# twometertx.net
KiCad netlist of a schematic drawn in EAGLE
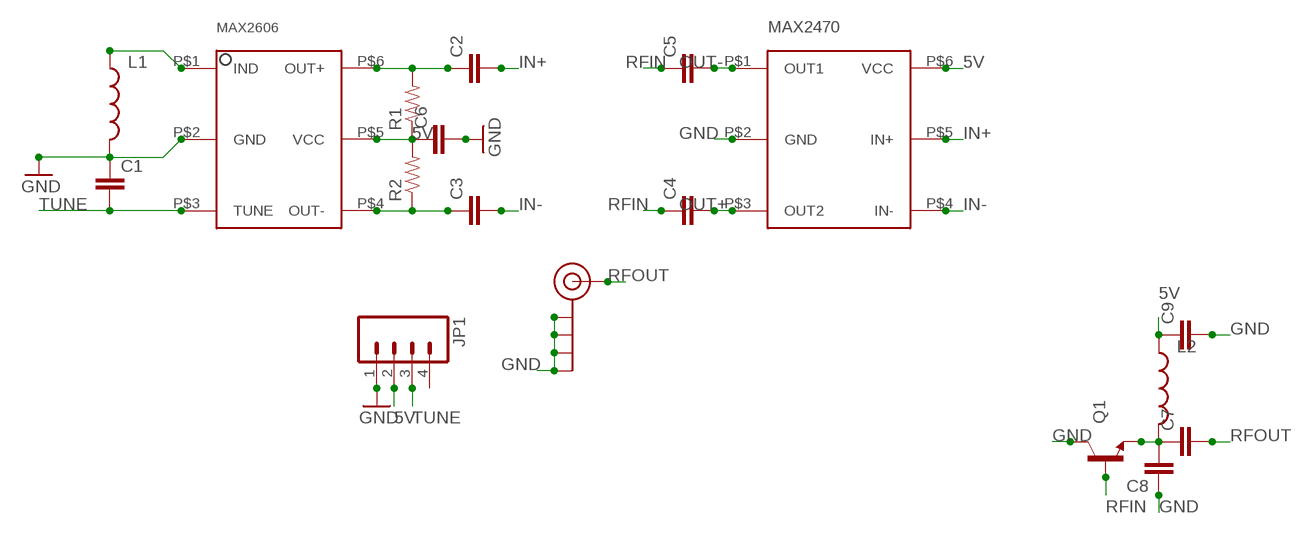
[diagram p0: schematic, sheet 1]

(export (version "E")
  (design (tool "Eeschema 10.0.6"))
  (components
    (comp (ref "C1")
      (value "CAP0805")
      (footprint "eagle-import:0805")
      (libsource (lib "eagle-import") (part "CAP0805"))
    )
    (comp (ref "C2")
      (value "CAP0805")
      (footprint "eagle-import:0805")
      (libsource (lib "eagle-import") (part "CAP0805"))
    )
    (comp (ref "C3")
      (value "CAP0805")
      (footprint "eagle-import:0805")
      (libsource (lib "eagle-import") (part "CAP0805"))
    )
    (comp (ref "C4")
      (value "CAP0805")
      (footprint "eagle-import:0805")
      (libsource (lib "eagle-import") (part "CAP0805"))
    )
    (comp (ref "C5")
      (value "CAP0805")
      (footprint "eagle-import:0805")
      (libsource (lib "eagle-import") (part "CAP0805"))
    )
    (comp (ref "C6")
      (value "CAP0805")
      (footprint "eagle-import:0805")
      (libsource (lib "eagle-import") (part "CAP0805"))
    )
    (comp (ref "C7")
      (value "CAP0805")
      (footprint "eagle-import:0805")
      (libsource (lib "eagle-import") (part "CAP0805"))
    )
    (comp (ref "C8")
      (value "CAP0805")
      (footprint "eagle-import:0805")
      (libsource (lib "eagle-import") (part "CAP0805"))
    )
    (comp (ref "C9")
      (value "CAP0805")
      (footprint "eagle-import:0805")
      (libsource (lib "eagle-import") (part "CAP0805"))
    )
    (comp (ref "J$1")
      (value "SMA_EDGE")
      (footprint "eagle-import:SMA-EDGE")
      (libsource (lib "eagle-import") (part "SMA_EDGE"))
    )
    (comp (ref "JP1")
      (value "M04LONGPADS")
      (footprint "eagle-import:1X04_LONGPADS")
      (libsource (lib "eagle-import") (part "M04LONGPADS"))
    )
    (comp (ref "L1")
      (value "INDUCTOR0805")
      (footprint "eagle-import:0805")
      (libsource (lib "eagle-import") (part "INDUCTOR0805"))
    )
    (comp (ref "L2")
      (value "INDUCTOR0805")
      (footprint "eagle-import:0805")
      (libsource (lib "eagle-import") (part "INDUCTOR0805"))
    )
    (comp (ref "Q1")
      (value "TRANSISTOR_NPNSOT89")
      (footprint "eagle-import:SOT89")
      (libsource (lib "eagle-import") (part "TRANSISTOR_NPNSOT89"))
    )
    (comp (ref "R1")
      (value "RESISTOR0805-RES")
      (footprint "eagle-import:0805")
      (libsource (lib "eagle-import") (part "RESISTOR0805-RES"))
    )
    (comp (ref "R2")
      (value "RESISTOR0805-RES")
      (footprint "eagle-import:0805")
      (libsource (lib "eagle-import") (part "RESISTOR0805-RES"))
    )
    (comp (ref "U$1")
      (value "MAX2606")
      (footprint "eagle-import:MAX2606")
      (libsource (lib "eagle-import") (part "MAX2606"))
    )
    (comp (ref "U$2")
      (value "MAX2470")
      (footprint "eagle-import:MAX2470")
      (libsource (lib "eagle-import") (part "MAX2470"))
    )
  )
  (nets
    (net (code "1") (name "/5V") (class "Default")
      (node (ref "C6") (pin "1") (pinfunction "1_1") (pintype "passive"))
      (node (ref "C9") (pin "1") (pinfunction "1_1") (pintype "passive"))
      (node (ref "JP1") (pin "2") (pinfunction "2_2") (pintype "passive"))
      (node (ref "L2") (pin "1") (pinfunction "1_1") (pintype "passive"))
      (node (ref "R1") (pin "1") (pinfunction "1_1") (pintype "passive"))
      (node (ref "R2") (pin "2") (pinfunction "2_2") (pintype "passive"))
      (node (ref "U$1") (pin "P$5") (pinfunction "VCC_P$5") (pintype "bidirectional"))
      (node (ref "U$2") (pin "P$6") (pinfunction "VCC_P$6") (pintype "bidirectional"))
    )
    (net (code "2") (name "/IN+") (class "Default")
      (node (ref "C2") (pin "2") (pinfunction "2_2") (pintype "passive"))
      (node (ref "U$2") (pin "P$5") (pinfunction "IN+_P$5") (pintype "bidirectional"))
    )
    (net (code "3") (name "/IN-") (class "Default")
      (node (ref "C3") (pin "2") (pinfunction "2_2") (pintype "passive"))
      (node (ref "U$2") (pin "P$4") (pinfunction "IN-_P$4") (pintype "bidirectional"))
    )
    (net (code "4") (name "/OUT+") (class "Default")
      (node (ref "C4") (pin "2") (pinfunction "2_2") (pintype "passive"))
      (node (ref "U$2") (pin "P$3") (pinfunction "OUT2_P$3") (pintype "bidirectional"))
    )
    (net (code "5") (name "/OUT-") (class "Default")
      (node (ref "C5") (pin "2") (pinfunction "2_2") (pintype "passive"))
      (node (ref "U$2") (pin "P$1") (pinfunction "OUT1_P$1") (pintype "bidirectional"))
    )
    (net (code "6") (name "/RFIN") (class "Default")
      (node (ref "C4") (pin "1") (pinfunction "1_1") (pintype "passive"))
      (node (ref "C5") (pin "1") (pinfunction "1_1") (pintype "passive"))
      (node (ref "Q1") (pin "1") (pinfunction "B_1") (pintype "passive"))
    )
    (net (code "7") (name "/RFOUT") (class "Default")
      (node (ref "C7") (pin "2") (pinfunction "2_2") (pintype "passive"))
      (node (ref "J$1") (pin "SIG") (pinfunction "SIGNAL_SIG") (pintype "bidirectional"))
    )
    (net (code "8") (name "/TUNE") (class "Default")
      (node (ref "C1") (pin "2") (pinfunction "2_2") (pintype "passive"))
      (node (ref "JP1") (pin "3") (pinfunction "3_3") (pintype "passive"))
      (node (ref "U$1") (pin "P$3") (pinfunction "TUNE_P$3") (pintype "bidirectional"))
    )
    (net (code "9") (name "GND") (class "Default")
      (node (ref "C1") (pin "1") (pinfunction "1_1") (pintype "passive"))
      (node (ref "C6") (pin "2") (pinfunction "2_2") (pintype "passive"))
      (node (ref "C8") (pin "1") (pinfunction "1_1") (pintype "passive"))
      (node (ref "C9") (pin "2") (pinfunction "2_2") (pintype "passive"))
      (node (ref "J$1") (pin "GND@0") (pinfunction "GND_GND@0") (pintype "bidirectional"))
      (node (ref "J$1") (pin "GND@1") (pinfunction "GND_GND@1") (pintype "bidirectional"))
      (node (ref "J$1") (pin "GND@2") (pinfunction "GND_GND@2") (pintype "bidirectional"))
      (node (ref "J$1") (pin "GND@3") (pinfunction "GND_GND@3") (pintype "bidirectional"))
      (node (ref "JP1") (pin "1") (pinfunction "1_1") (pintype "passive"))
      (node (ref "L1") (pin "2") (pinfunction "2_2") (pintype "passive"))
      (node (ref "Q1") (pin "2") (pinfunction "C_2") (pintype "passive"))
      (node (ref "U$1") (pin "P$2") (pinfunction "GND_P$2") (pintype "bidirectional"))
      (node (ref "U$2") (pin "P$2") (pinfunction "GND_P$2") (pintype "bidirectional"))
    )
    (net (code "10") (name "Net-(Q1-E)") (class "Default")
      (node (ref "C7") (pin "1") (pinfunction "1_1") (pintype "passive"))
      (node (ref "C8") (pin "2") (pinfunction "2_2") (pintype "passive"))
      (node (ref "L2") (pin "2") (pinfunction "2_2") (pintype "passive"))
      (node (ref "Q1") (pin "3") (pinfunction "E_3") (pintype "passive"))
    )
    (net (code "11") (name "Net-(U$1-IND)") (class "Default")
      (node (ref "L1") (pin "1") (pinfunction "1_1") (pintype "passive"))
      (node (ref "U$1") (pin "P$1") (pinfunction "IND_P$1") (pintype "bidirectional"))
    )
    (net (code "12") (name "Net-(U$1-OUT+)") (class "Default")
      (node (ref "C2") (pin "1") (pinfunction "1_1") (pintype "passive"))
      (node (ref "R1") (pin "2") (pinfunction "2_2") (pintype "passive"))
      (node (ref "U$1") (pin "P$6") (pinfunction "OUT+_P$6") (pintype "bidirectional"))
    )
    (net (code "13") (name "Net-(U$1-OUT-)") (class "Default")
      (node (ref "C3") (pin "1") (pinfunction "1_1") (pintype "passive"))
      (node (ref "R2") (pin "1") (pinfunction "1_1") (pintype "passive"))
      (node (ref "U$1") (pin "P$4") (pinfunction "OUT-_P$4") (pintype "bidirectional"))
    )
    (net (code "14") (name "unconnected-(JP1-Pad4)") (class "Default")
      (node (ref "JP1") (pin "4") (pinfunction "4_4") (pintype "passive"))
    )
  )
)
